# PSU_ADM660AR_DOUBLER.net
KiCad netlist of a schematic drawn in Altium Designer
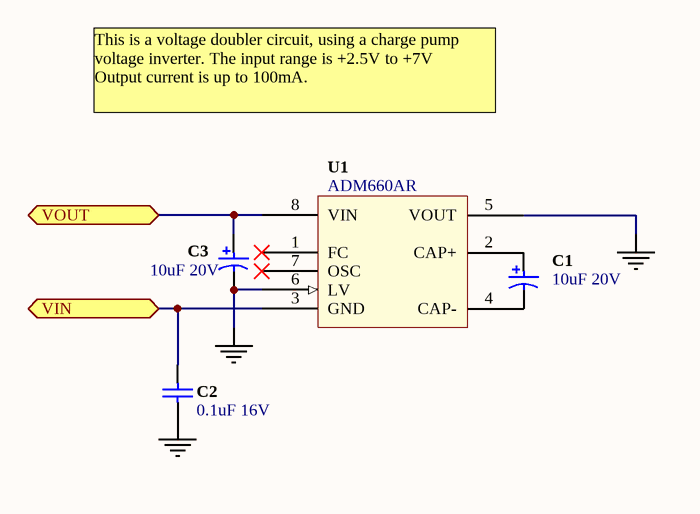
[diagram p0: PSU_ADM660AR_DOUBLER.SchDoc]

(export (version "E")
  (design (tool "Eeschema 10.0.6"))
  (components
    (comp (ref "C1")
      (value "10uF 20V")
      (footprint "CAPC3528-STAR")
      (description "Capacitor, Tantalum, 10uF 10% 20V MCCT-B (3528)")
      (fields (field (name "TOLERANCE") "10 %"))
      (libsource (lib "altium-import") (part "root_0_CAP-P_"))
    )
    (comp (ref "C2")
      (value "0.1uF 16V")
      (footprint "CAPC1005-STAR")
      (description "Capacitor, Ceramic, 0.1uF 10% 16V 0402 (1005) X7R")
      (fields (field (name "TOLERANCE") "10 %"))
      (libsource (lib "altium-import") (part "root_0_CAP-NP_"))
    )
    (comp (ref "C3")
      (value "10uF 20V")
      (footprint "CAPC3528-STAR")
      (description "Capacitor, Tantalum, 10uF 10% 20V MCCT-B (3528)")
      (fields (field (name "TOLERANCE") "10 %"))
      (libsource (lib "altium-import") (part "root_0_CAP-P_"))
    )
    (comp (ref "U1")
      (value "ADM660AR")
      (footprint "SOIC127P600-8")
      (description "ADM660AR, Switched-Capacitor Voltage Converter/Inverter, 1.5-7V, 100mA, SO8")
      (libsource (lib "AltiumDesignLibrary") (part "ADM660AR"))
    )
  )
  (nets
    (net (code "1") (name "/VIN") (class "Default")
      (node (ref "C2") (pin "1") (pinfunction "1_1") (pintype "passive"))
      (node (ref "U1") (pin "3") (pinfunction "GND_3") (pintype "passive"))
    )
    (net (code "2") (name "/VOUT") (class "Default")
      (node (ref "C3") (pin "1") (pinfunction "1_1") (pintype "passive"))
      (node (ref "U1") (pin "8") (pinfunction "VIN_8") (pintype "passive"))
    )
    (net (code "3") (name "GND") (class "Default")
      (node (ref "C2") (pin "2") (pinfunction "2_2") (pintype "passive"))
      (node (ref "C3") (pin "2") (pinfunction "2_2") (pintype "passive"))
      (node (ref "U1") (pin "5") (pinfunction "VOUT_5") (pintype "passive"))
      (node (ref "U1") (pin "6") (pinfunction "LV_6") (pintype "input"))
    )
    (net (code "4") (name "Net-(U1-CAP+)") (class "Default")
      (node (ref "C1") (pin "1") (pinfunction "1_1") (pintype "passive"))
      (node (ref "U1") (pin "2") (pinfunction "CAP+_2") (pintype "passive"))
    )
    (net (code "5") (name "Net-(U1-CAP-)") (class "Default")
      (node (ref "C1") (pin "2") (pinfunction "2_2") (pintype "passive"))
      (node (ref "U1") (pin "4") (pinfunction "CAP-_4") (pintype "passive"))
    )
    (net (code "6") (name "unconnected-(U1-FC-Pad1)") (class "Default")
      (node (ref "U1") (pin "1") (pinfunction "FC_1") (pintype "passive+no_connect"))
    )
    (net (code "7") (name "unconnected-(U1-OSC-Pad7)") (class "Default")
      (node (ref "U1") (pin "7") (pinfunction "OSC_7") (pintype "passive+no_connect"))
    )
  )
)
